# OttoPi08-RPi3AHAT.net
KiCad netlist of a schematic drawn in EAGLE
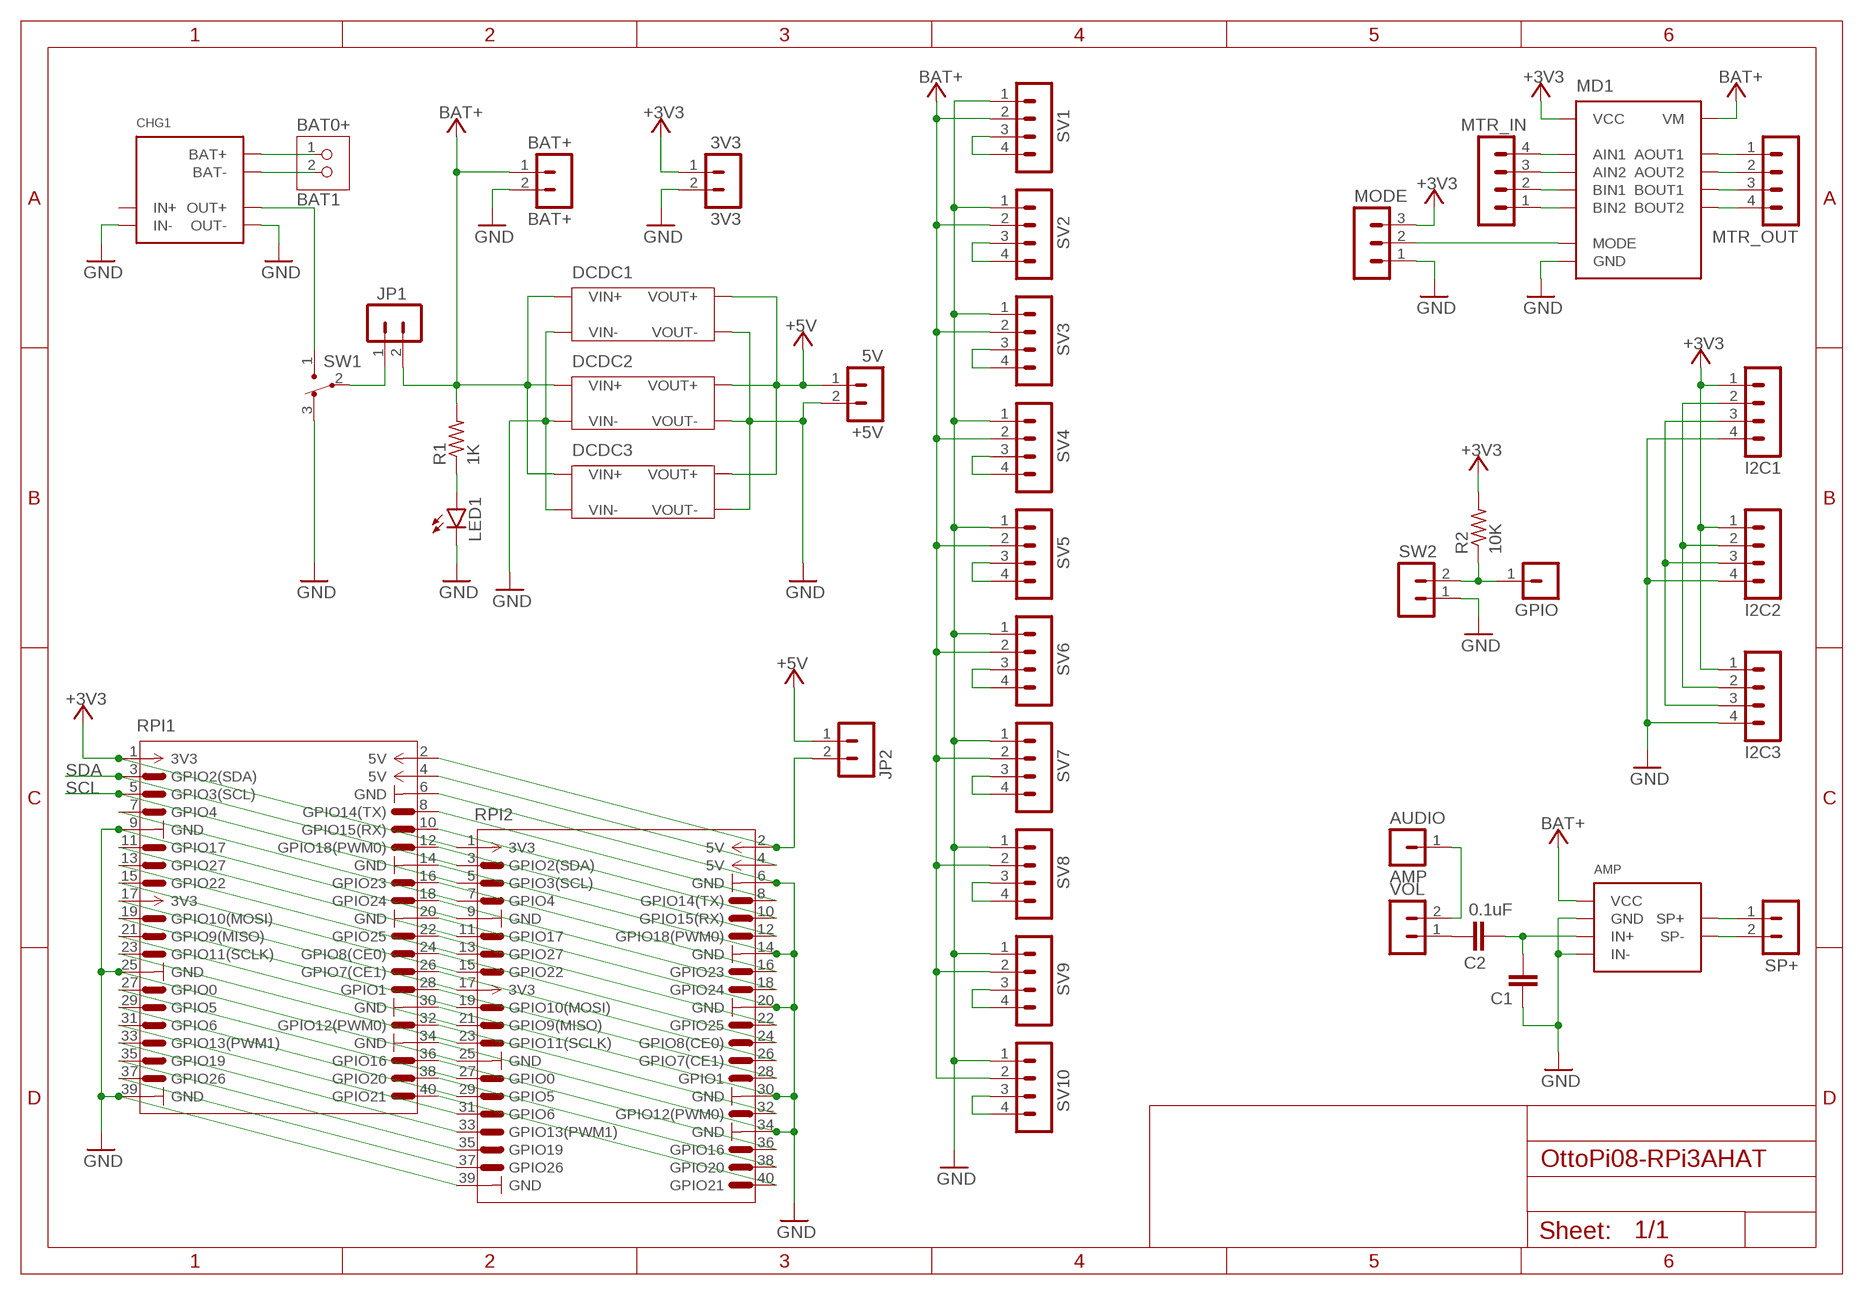
[diagram p0: schematic, sheet 1]

(export (version "E")
  (design (tool "Eeschema 10.0.6"))
  (components
    (comp (ref "+5V")
      (value "5V")
      (footprint "eagle-import:PINHEAD-MA02-1")
      (libsource (lib "eagle-import") (part "PINHEAD-MA02-1"))
    )
    (comp (ref "3V3")
      (value "3V3")
      (footprint "eagle-import:PINHEAD-MA02-1")
      (libsource (lib "eagle-import") (part "PINHEAD-MA02-1"))
    )
    (comp (ref "AMP")
      (value "AMP")
      (footprint "eagle-import:PAM8012MOD-A")
      (libsource (lib "eagle-import") (part "PAM8012MOD"))
    )
    (comp (ref "AUDIO")
      (value "AMP")
      (footprint "eagle-import:PINHEAD-MA01-1")
      (libsource (lib "eagle-import") (part "PINHEAD-MA01-1"))
    )
    (comp (ref "BAT+")
      (value "BAT+")
      (footprint "eagle-import:PINHEAD-MA02-1")
      (libsource (lib "eagle-import") (part "PINHEAD-MA02-1"))
    )
    (comp (ref "BAT0+")
      (value "BAT1")
      (footprint "eagle-import:JST-PH2")
      (libsource (lib "eagle-import") (part "JST-PH2"))
    )
    (comp (ref "C1")
      (value "C-EU025-024X044")
      (footprint "eagle-import:C025-024X044")
      (libsource (lib "eagle-import") (part "C-EU025-024X044"))
    )
    (comp (ref "C2")
      (value "0.1uF")
      (footprint "eagle-import:C025-024X044")
      (libsource (lib "eagle-import") (part "C-EU025-024X044"))
    )
    (comp (ref "CHG1")
      (value "TP4056MOD1")
      (footprint "eagle-import:TP4056MOD1")
      (libsource (lib "eagle-import") (part "TP4056MOD1"))
    )
    (comp (ref "DCDC1")
      (value "DCDC-MT3608-MOD")
      (footprint "eagle-import:DCDC-MT3608-MOD1")
      (libsource (lib "eagle-import") (part "DCDC-MT3608-MOD"))
    )
    (comp (ref "DCDC2")
      (value "DCDC-SX1308-MOD1")
      (footprint "eagle-import:DCDC-SX1308-MOD1")
      (libsource (lib "eagle-import") (part "DCDC-SX1308-MOD1"))
    )
    (comp (ref "DCDC3")
      (value "DCDC-MT3608-MODUSB")
      (footprint "eagle-import:DCDC-MT3608-MOD2-USB")
      (libsource (lib "eagle-import") (part "DCDC-MT3608-MODUSB"))
    )
    (comp (ref "GPIO")
      (value "PINHEAD-MA01-1")
      (footprint "eagle-import:PINHEAD-MA01-1")
      (libsource (lib "eagle-import") (part "PINHEAD-MA01-1"))
    )
    (comp (ref "I2C1")
      (value "PINHEAD-MA04-1")
      (footprint "eagle-import:PINHEAD-MA04-1")
      (libsource (lib "eagle-import") (part "PINHEAD-MA04-1"))
    )
    (comp (ref "I2C2")
      (value "PINHEAD-MA04-1")
      (footprint "eagle-import:PINHEAD-MA04-1")
      (libsource (lib "eagle-import") (part "PINHEAD-MA04-1"))
    )
    (comp (ref "I2C3")
      (value "PINHEAD-MA04-1")
      (footprint "eagle-import:PINHEAD-MA04-1")
      (libsource (lib "eagle-import") (part "PINHEAD-MA04-1"))
    )
    (comp (ref "JP1")
      (value "PINHEAD-MA02-1")
      (footprint "eagle-import:PINHEAD-MA02-1")
      (libsource (lib "eagle-import") (part "PINHEAD-MA02-1"))
    )
    (comp (ref "JP2")
      (value "PINHEAD-MA02-1")
      (footprint "eagle-import:PINHEAD-MA02-1")
      (libsource (lib "eagle-import") (part "PINHEAD-MA02-1"))
    )
    (comp (ref "LED1")
      (value "LED3MM")
      (footprint "eagle-import:LED3MM")
      (libsource (lib "eagle-import") (part "LED3MM"))
    )
    (comp (ref "MD1")
      (value "DRV8835MOD")
      (footprint "eagle-import:DRV8835MOD")
      (libsource (lib "eagle-import") (part "DRV8835MOD"))
    )
    (comp (ref "MODE")
      (value "PINHEAD-MA03-1")
      (footprint "eagle-import:PINHEAD-MA03-1")
      (libsource (lib "eagle-import") (part "PINHEAD-MA03-1"))
    )
    (comp (ref "MTR_IN")
      (value "PINHEAD-MA04-1")
      (footprint "eagle-import:PINHEAD-MA04-1")
      (libsource (lib "eagle-import") (part "PINHEAD-MA04-1"))
    )
    (comp (ref "MTR_OUT")
      (value "PINHEAD-MA04-1")
      (footprint "eagle-import:PINHEAD-MA04-1")
      (libsource (lib "eagle-import") (part "PINHEAD-MA04-1"))
    )
    (comp (ref "R1")
      (value "1K")
      (footprint "eagle-import:0204_7")
      (libsource (lib "eagle-import") (part "R-US_0204/7"))
    )
    (comp (ref "R2")
      (value "10K")
      (footprint "eagle-import:0204_7")
      (libsource (lib "eagle-import") (part "R-US_0204/7"))
    )
    (comp (ref "RPI1")
      (value "RPI-PIN")
      (footprint "eagle-import:RPI-PIN")
      (libsource (lib "eagle-import") (part "RPI-PIN"))
    )
    (comp (ref "RPI2")
      (value "RPI-PIN")
      (footprint "eagle-import:RPI-PIN")
      (libsource (lib "eagle-import") (part "RPI-PIN"))
    )
    (comp (ref "SP+")
      (value "PINHEAD-MA02-1")
      (footprint "eagle-import:PINHEAD-MA02-1")
      (libsource (lib "eagle-import") (part "PINHEAD-MA02-1"))
    )
    (comp (ref "SV1")
      (value "PINHEAD-MA04-1")
      (footprint "eagle-import:PINHEAD-MA04-1")
      (libsource (lib "eagle-import") (part "PINHEAD-MA04-1"))
    )
    (comp (ref "SV2")
      (value "PINHEAD-MA04-1")
      (footprint "eagle-import:PINHEAD-MA04-1")
      (libsource (lib "eagle-import") (part "PINHEAD-MA04-1"))
    )
    (comp (ref "SV3")
      (value "PINHEAD-MA04-1")
      (footprint "eagle-import:PINHEAD-MA04-1")
      (libsource (lib "eagle-import") (part "PINHEAD-MA04-1"))
    )
    (comp (ref "SV4")
      (value "PINHEAD-MA04-1")
      (footprint "eagle-import:PINHEAD-MA04-1")
      (libsource (lib "eagle-import") (part "PINHEAD-MA04-1"))
    )
    (comp (ref "SV5")
      (value "PINHEAD-MA04-1")
      (footprint "eagle-import:PINHEAD-MA04-1")
      (libsource (lib "eagle-import") (part "PINHEAD-MA04-1"))
    )
    (comp (ref "SV6")
      (value "PINHEAD-MA04-1")
      (footprint "eagle-import:PINHEAD-MA04-1")
      (libsource (lib "eagle-import") (part "PINHEAD-MA04-1"))
    )
    (comp (ref "SV7")
      (value "PINHEAD-MA04-1")
      (footprint "eagle-import:PINHEAD-MA04-1")
      (libsource (lib "eagle-import") (part "PINHEAD-MA04-1"))
    )
    (comp (ref "SV8")
      (value "PINHEAD-MA04-1")
      (footprint "eagle-import:PINHEAD-MA04-1")
      (libsource (lib "eagle-import") (part "PINHEAD-MA04-1"))
    )
    (comp (ref "SV9")
      (value "PINHEAD-MA04-1")
      (footprint "eagle-import:PINHEAD-MA04-1")
      (libsource (lib "eagle-import") (part "PINHEAD-MA04-1"))
    )
    (comp (ref "SV10")
      (value "PINHEAD-MA04-1")
      (footprint "eagle-import:PINHEAD-MA04-1")
      (libsource (lib "eagle-import") (part "PINHEAD-MA04-1"))
    )
    (comp (ref "SW1")
      (value "SW3-1")
      (footprint "eagle-import:SW3-1")
      (fields (field (name "MF") "HiLetgo"))
      (libsource (lib "eagle-import") (part "SW3-1"))
    )
    (comp (ref "SW2")
      (value "PINHEAD-MA02-1")
      (footprint "eagle-import:PINHEAD-MA02-1")
      (libsource (lib "eagle-import") (part "PINHEAD-MA02-1"))
    )
    (comp (ref "VOL")
      (value "PINHEAD-MA02-1")
      (footprint "eagle-import:PINHEAD-MA02-1")
      (libsource (lib "eagle-import") (part "PINHEAD-MA02-1"))
    )
  )
  (nets
    (net (code "1") (name "+3V3") (class "Default")
      (node (ref "3V3") (pin "1") (pinfunction "1_1") (pintype "passive"))
      (node (ref "I2C1") (pin "1") (pinfunction "1_1") (pintype "passive"))
      (node (ref "I2C2") (pin "1") (pinfunction "1_1") (pintype "passive"))
      (node (ref "I2C3") (pin "1") (pinfunction "1_1") (pintype "passive"))
      (node (ref "MD1") (pin "VCC") (pinfunction "VCC_VCC") (pintype "input"))
      (node (ref "MODE") (pin "3") (pinfunction "3_3") (pintype "passive"))
      (node (ref "R2") (pin "2") (pinfunction "2_2") (pintype "passive"))
      (node (ref "RPI1") (pin "1") (pinfunction "3V3_1") (pintype "passive"))
      (node (ref "RPI2") (pin "1") (pinfunction "3V3_1") (pintype "passive"))
    )
    (net (code "2") (name "+5V") (class "Default")
      (node (ref "+5V") (pin "1") (pinfunction "1_1") (pintype "passive"))
      (node (ref "DCDC1") (pin "VOUT+") (pinfunction "VOUT+_VOUT+") (pintype "power_in"))
      (node (ref "DCDC2") (pin "VOUT+") (pinfunction "VOUT+_VOUT+") (pintype "power_in"))
      (node (ref "DCDC3") (pin "VOUT+") (pinfunction "VOUT+_VOUT+") (pintype "power_in"))
      (node (ref "JP2") (pin "1") (pinfunction "1_1") (pintype "passive"))
    )
    (net (code "3") (name "/SCL") (class "Default")
      (node (ref "I2C1") (pin "3") (pinfunction "3_3") (pintype "passive"))
      (node (ref "I2C2") (pin "3") (pinfunction "3_3") (pintype "passive"))
      (node (ref "I2C3") (pin "3") (pinfunction "3_3") (pintype "passive"))
      (node (ref "RPI1") (pin "5") (pinfunction "GPIO3(SCL)_5") (pintype "passive"))
      (node (ref "RPI2") (pin "5") (pinfunction "GPIO3(SCL)_5") (pintype "passive"))
    )
    (net (code "4") (name "/SDA") (class "Default")
      (node (ref "I2C1") (pin "2") (pinfunction "2_2") (pintype "passive"))
      (node (ref "I2C2") (pin "2") (pinfunction "2_2") (pintype "passive"))
      (node (ref "I2C3") (pin "2") (pinfunction "2_2") (pintype "passive"))
      (node (ref "RPI1") (pin "3") (pinfunction "GPIO2(SDA)_3") (pintype "passive"))
      (node (ref "RPI2") (pin "3") (pinfunction "GPIO2(SDA)_3") (pintype "passive"))
    )
    (net (code "5") (name "BAT+") (class "Default")
      (node (ref "AMP") (pin "V+") (pinfunction "VCC_V+") (pintype "passive"))
      (node (ref "BAT+") (pin "1") (pinfunction "1_1") (pintype "passive"))
      (node (ref "DCDC1") (pin "VIN+") (pinfunction "VIN+_VIN+") (pintype "power_in"))
      (node (ref "DCDC2") (pin "VIN+") (pinfunction "VIN+_VIN+") (pintype "power_in"))
      (node (ref "DCDC3") (pin "VIN+") (pinfunction "VIN+_VIN+") (pintype "power_in"))
      (node (ref "JP1") (pin "2") (pinfunction "2_2") (pintype "passive"))
      (node (ref "MD1") (pin "VM") (pinfunction "VM_VM") (pintype "input"))
      (node (ref "R1") (pin "2") (pinfunction "2_2") (pintype "passive"))
      (node (ref "SV1") (pin "2") (pinfunction "2_2") (pintype "passive"))
      (node (ref "SV10") (pin "2") (pinfunction "2_2") (pintype "passive"))
      (node (ref "SV2") (pin "2") (pinfunction "2_2") (pintype "passive"))
      (node (ref "SV3") (pin "2") (pinfunction "2_2") (pintype "passive"))
      (node (ref "SV4") (pin "2") (pinfunction "2_2") (pintype "passive"))
      (node (ref "SV5") (pin "2") (pinfunction "2_2") (pintype "passive"))
      (node (ref "SV6") (pin "2") (pinfunction "2_2") (pintype "passive"))
      (node (ref "SV7") (pin "2") (pinfunction "2_2") (pintype "passive"))
      (node (ref "SV8") (pin "2") (pinfunction "2_2") (pintype "passive"))
      (node (ref "SV9") (pin "2") (pinfunction "2_2") (pintype "passive"))
    )
    (net (code "6") (name "GND") (class "Default")
      (node (ref "+5V") (pin "2") (pinfunction "2_2") (pintype "passive"))
      (node (ref "3V3") (pin "2") (pinfunction "2_2") (pintype "passive"))
      (node (ref "AMP") (pin "GND") (pinfunction "GND_GND") (pintype "passive"))
      (node (ref "AMP") (pin "IN-") (pinfunction "IN-_IN-") (pintype "input"))
      (node (ref "BAT+") (pin "2") (pinfunction "2_2") (pintype "passive"))
      (node (ref "C1") (pin "1") (pinfunction "1_1") (pintype "passive"))
      (node (ref "CHG1") (pin "IN-") (pinfunction "IN-_IN-") (pintype "passive"))
      (node (ref "CHG1") (pin "OUT-") (pinfunction "OUT-_OUT-") (pintype "passive"))
      (node (ref "DCDC1") (pin "VIN-") (pinfunction "VIN-_VIN-") (pintype "power_in"))
      (node (ref "DCDC1") (pin "VOUT-") (pinfunction "VOUT-_VOUT-") (pintype "power_in"))
      (node (ref "DCDC2") (pin "VIN-") (pinfunction "VIN-_VIN-") (pintype "power_in"))
      (node (ref "DCDC2") (pin "VOUT-") (pinfunction "VOUT-_VOUT-") (pintype "power_in"))
      (node (ref "DCDC3") (pin "VIN-") (pinfunction "VIN-_VIN-") (pintype "power_in"))
      (node (ref "DCDC3") (pin "VOUT-") (pinfunction "VOUT-_VOUT-") (pintype "power_in"))
      (node (ref "I2C1") (pin "4") (pinfunction "4_4") (pintype "passive"))
      (node (ref "I2C2") (pin "4") (pinfunction "4_4") (pintype "passive"))
      (node (ref "I2C3") (pin "4") (pinfunction "4_4") (pintype "passive"))
      (node (ref "LED1") (pin "K") (pinfunction "C_K") (pintype "passive"))
      (node (ref "MD1") (pin "GND") (pinfunction "GND_GND") (pintype "power_in"))
      (node (ref "MODE") (pin "1") (pinfunction "1_1") (pintype "passive"))
      (node (ref "RPI1") (pin "14") (pinfunction "GND_14") (pintype "passive"))
      (node (ref "RPI1") (pin "20") (pinfunction "GND_20") (pintype "passive"))
      (node (ref "RPI1") (pin "25") (pinfunction "GND_25") (pintype "passive"))
      (node (ref "RPI1") (pin "30") (pinfunction "GND_30") (pintype "passive"))
      (node (ref "RPI1") (pin "34") (pinfunction "GND_34") (pintype "passive"))
      (node (ref "RPI1") (pin "39") (pinfunction "GND_39") (pintype "passive"))
      (node (ref "RPI1") (pin "6") (pinfunction "GND_6") (pintype "passive"))
      (node (ref "RPI1") (pin "9") (pinfunction "GND_9") (pintype "passive"))
      (node (ref "RPI2") (pin "14") (pinfunction "GND_14") (pintype "passive"))
      (node (ref "RPI2") (pin "20") (pinfunction "GND_20") (pintype "passive"))
      (node (ref "RPI2") (pin "25") (pinfunction "GND_25") (pintype "passive"))
      (node (ref "RPI2") (pin "30") (pinfunction "GND_30") (pintype "passive"))
      (node (ref "RPI2") (pin "34") (pinfunction "GND_34") (pintype "passive"))
      (node (ref "RPI2") (pin "39") (pinfunction "GND_39") (pintype "passive"))
      (node (ref "RPI2") (pin "6") (pinfunction "GND_6") (pintype "passive"))
      (node (ref "RPI2") (pin "9") (pinfunction "GND_9") (pintype "passive"))
      (node (ref "SV1") (pin "1") (pinfunction "1_1") (pintype "passive"))
      (node (ref "SV10") (pin "1") (pinfunction "1_1") (pintype "passive"))
      (node (ref "SV2") (pin "1") (pinfunction "1_1") (pintype "passive"))
      (node (ref "SV3") (pin "1") (pinfunction "1_1") (pintype "passive"))
      (node (ref "SV4") (pin "1") (pinfunction "1_1") (pintype "passive"))
      (node (ref "SV5") (pin "1") (pinfunction "1_1") (pintype "passive"))
      (node (ref "SV6") (pin "1") (pinfunction "1_1") (pintype "passive"))
      (node (ref "SV7") (pin "1") (pinfunction "1_1") (pintype "passive"))
      (node (ref "SV8") (pin "1") (pinfunction "1_1") (pintype "passive"))
      (node (ref "SV9") (pin "1") (pinfunction "1_1") (pintype "passive"))
      (node (ref "SW1") (pin "3") (pinfunction "3_3") (pintype "passive"))
      (node (ref "SW2") (pin "1") (pinfunction "1_1") (pintype "passive"))
    )
    (net (code "7") (name "Net-(AMP-PadIN+)") (class "Default")
      (node (ref "AMP") (pin "IN+") (pinfunction "IN+_IN+") (pintype "input"))
      (node (ref "C1") (pin "2") (pinfunction "2_2") (pintype "passive"))
      (node (ref "C2") (pin "1") (pinfunction "1_1") (pintype "passive"))
    )
    (net (code "8") (name "Net-(AMP-SP+)") (class "Default")
      (node (ref "AMP") (pin "SP+@1") (pinfunction "SP+_SP+@1") (pintype "output"))
      (node (ref "SP+") (pin "1") (pinfunction "1_1") (pintype "passive"))
    )
    (net (code "9") (name "Net-(AMP-SP-)") (class "Default")
      (node (ref "AMP") (pin "SP-@1") (pinfunction "SP-_SP-@1") (pintype "output"))
      (node (ref "SP+") (pin "2") (pinfunction "2_2") (pintype "passive"))
    )
    (net (code "10") (name "Net-(AUDIO-Pad1)") (class "Default")
      (node (ref "AUDIO") (pin "1") (pinfunction "1_1") (pintype "passive"))
      (node (ref "VOL") (pin "2") (pinfunction "2_2") (pintype "passive"))
    )
    (net (code "11") (name "Net-(BAT0+-Pad1)") (class "Default")
      (node (ref "BAT0+") (pin "1") (pinfunction "1_1") (pintype "passive"))
      (node (ref "CHG1") (pin "BAT+") (pinfunction "BAT+_BAT+") (pintype "passive"))
    )
    (net (code "12") (name "Net-(BAT0+-Pad2)") (class "Default")
      (node (ref "BAT0+") (pin "2") (pinfunction "2_2") (pintype "passive"))
      (node (ref "CHG1") (pin "BAT-") (pinfunction "BAT-_BAT-") (pintype "passive"))
    )
    (net (code "13") (name "Net-(C2-Pad2)") (class "Default")
      (node (ref "C2") (pin "2") (pinfunction "2_2") (pintype "passive"))
      (node (ref "VOL") (pin "1") (pinfunction "1_1") (pintype "passive"))
    )
    (net (code "14") (name "Net-(CHG1-PadOUT+)") (class "Default")
      (node (ref "CHG1") (pin "OUT+") (pinfunction "OUT+_OUT+") (pintype "passive"))
      (node (ref "SW1") (pin "1") (pinfunction "1_1") (pintype "passive"))
    )
    (net (code "15") (name "Net-(GPIO-Pad1)") (class "Default")
      (node (ref "GPIO") (pin "1") (pinfunction "1_1") (pintype "passive"))
      (node (ref "R2") (pin "1") (pinfunction "1_1") (pintype "passive"))
      (node (ref "SW2") (pin "2") (pinfunction "2_2") (pintype "passive"))
    )
    (net (code "16") (name "Net-(JP1-Pad1)") (class "Default")
      (node (ref "JP1") (pin "1") (pinfunction "1_1") (pintype "passive"))
      (node (ref "SW1") (pin "2") (pinfunction "2_2") (pintype "passive"))
    )
    (net (code "17") (name "Net-(JP2-Pad2)") (class "Default")
      (node (ref "JP2") (pin "2") (pinfunction "2_2") (pintype "passive"))
      (node (ref "RPI1") (pin "2") (pinfunction "5V_2") (pintype "passive"))
      (node (ref "RPI2") (pin "2") (pinfunction "5V_2") (pintype "passive"))
    )
    (net (code "18") (name "Net-(LED1-PadA)") (class "Default")
      (node (ref "LED1") (pin "A") (pinfunction "A_A") (pintype "passive"))
      (node (ref "R1") (pin "1") (pinfunction "1_1") (pintype "passive"))
    )
    (net (code "19") (name "Net-(MD1-PadAIN1)") (class "Default")
      (node (ref "MD1") (pin "AIN1") (pinfunction "AIN1_AIN1") (pintype "input"))
      (node (ref "MTR_IN") (pin "4") (pinfunction "4_4") (pintype "passive"))
    )
    (net (code "20") (name "Net-(MD1-PadAIN2)") (class "Default")
      (node (ref "MD1") (pin "AIN2") (pinfunction "AIN2_AIN2") (pintype "input"))
      (node (ref "MTR_IN") (pin "3") (pinfunction "3_3") (pintype "passive"))
    )
    (net (code "21") (name "Net-(MD1-PadAOUT1)") (class "Default")
      (node (ref "MD1") (pin "AOUT1") (pinfunction "AOUT1_AOUT1") (pintype "output"))
      (node (ref "MTR_OUT") (pin "1") (pinfunction "1_1") (pintype "passive"))
    )
    (net (code "22") (name "Net-(MD1-PadAOUT2)") (class "Default")
      (node (ref "MD1") (pin "AOUT2") (pinfunction "AOUT2_AOUT2") (pintype "output"))
      (node (ref "MTR_OUT") (pin "2") (pinfunction "2_2") (pintype "passive"))
    )
    (net (code "23") (name "Net-(MD1-PadBIN1)") (class "Default")
      (node (ref "MD1") (pin "BIN1") (pinfunction "BIN1_BIN1") (pintype "input"))
      (node (ref "MTR_IN") (pin "2") (pinfunction "2_2") (pintype "passive"))
    )
    (net (code "24") (name "Net-(MD1-PadBIN2)") (class "Default")
      (node (ref "MD1") (pin "BIN2") (pinfunction "BIN2_BIN2") (pintype "input"))
      (node (ref "MTR_IN") (pin "1") (pinfunction "1_1") (pintype "passive"))
    )
    (net (code "25") (name "Net-(MD1-PadBOUT1)") (class "Default")
      (node (ref "MD1") (pin "BOUT1") (pinfunction "BOUT1_BOUT1") (pintype "output"))
      (node (ref "MTR_OUT") (pin "3") (pinfunction "3_3") (pintype "passive"))
    )
    (net (code "26") (name "Net-(MD1-PadBOUT2)") (class "Default")
      (node (ref "MD1") (pin "BOUT2") (pinfunction "BOUT2_BOUT2") (pintype "output"))
      (node (ref "MTR_OUT") (pin "4") (pinfunction "4_4") (pintype "passive"))
    )
    (net (code "27") (name "Net-(MD1-PadMODE)") (class "Default")
      (node (ref "MD1") (pin "MODE") (pinfunction "MODE_MODE") (pintype "input"))
      (node (ref "MODE") (pin "2") (pinfunction "2_2") (pintype "passive"))
    )
    (net (code "28") (name "Net-(RPI1-3V3-Pad17)") (class "Default")
      (node (ref "RPI1") (pin "17") (pinfunction "3V3_17") (pintype "passive"))
      (node (ref "RPI2") (pin "17") (pinfunction "3V3_17") (pintype "passive"))
    )
    (net (code "29") (name "Net-(RPI1-5V-Pad4)") (class "Default")
      (node (ref "RPI1") (pin "4") (pinfunction "5V_4") (pintype "passive"))
      (node (ref "RPI2") (pin "4") (pinfunction "5V_4") (pintype "passive"))
    )
    (net (code "30") (name "Net-(RPI1-GPIO0)") (class "Default")
      (node (ref "RPI1") (pin "27") (pinfunction "GPIO0_27") (pintype "passive"))
      (node (ref "RPI2") (pin "27") (pinfunction "GPIO0_27") (pintype "passive"))
    )
    (net (code "31") (name "Net-(RPI1-GPIO1)") (class "Default")
      (node (ref "RPI1") (pin "28") (pinfunction "GPIO1_28") (pintype "passive"))
      (node (ref "RPI2") (pin "28") (pinfunction "GPIO1_28") (pintype "passive"))
    )
    (net (code "32") (name "Net-(RPI1-GPIO4)") (class "Default")
      (node (ref "RPI1") (pin "7") (pinfunction "GPIO4_7") (pintype "passive"))
      (node (ref "RPI2") (pin "7") (pinfunction "GPIO4_7") (pintype "passive"))
    )
    (net (code "33") (name "Net-(RPI1-GPIO5)") (class "Default")
      (node (ref "RPI1") (pin "29") (pinfunction "GPIO5_29") (pintype "passive"))
      (node (ref "RPI2") (pin "29") (pinfunction "GPIO5_29") (pintype "passive"))
    )
    (net (code "34") (name "Net-(RPI1-GPIO6)") (class "Default")
      (node (ref "RPI1") (pin "31") (pinfunction "GPIO6_31") (pintype "passive"))
      (node (ref "RPI2") (pin "31") (pinfunction "GPIO6_31") (pintype "passive"))
    )
    (net (code "35") (name "Net-(RPI1-GPIO7(CE1))") (class "Default")
      (node (ref "RPI1") (pin "26") (pinfunction "GPIO7(CE1)_26") (pintype "passive"))
      (node (ref "RPI2") (pin "26") (pinfunction "GPIO7(CE1)_26") (pintype "passive"))
    )
    (net (code "36") (name "Net-(RPI1-GPIO8(CE0))") (class "Default")
      (node (ref "RPI1") (pin "24") (pinfunction "GPIO8(CE0)_24") (pintype "passive"))
      (node (ref "RPI2") (pin "24") (pinfunction "GPIO8(CE0)_24") (pintype "passive"))
    )
    (net (code "37") (name "Net-(RPI1-GPIO9(MISO))") (class "Default")
      (node (ref "RPI1") (pin "21") (pinfunction "GPIO9(MISO)_21") (pintype "passive"))
      (node (ref "RPI2") (pin "21") (pinfunction "GPIO9(MISO)_21") (pintype "passive"))
    )
    (net (code "38") (name "Net-(RPI1-GPIO10(MOSI))") (class "Default")
      (node (ref "RPI1") (pin "19") (pinfunction "GPIO10(MOSI)_19") (pintype "passive"))
      (node (ref "RPI2") (pin "19") (pinfunction "GPIO10(MOSI)_19") (pintype "passive"))
    )
    (net (code "39") (name "Net-(RPI1-GPIO11(SCLK))") (class "Default")
      (node (ref "RPI1") (pin "23") (pinfunction "GPIO11(SCLK)_23") (pintype "passive"))
      (node (ref "RPI2") (pin "23") (pinfunction "GPIO11(SCLK)_23") (pintype "passive"))
    )
    (net (code "40") (name "Net-(RPI1-GPIO12(PWM0))") (class "Default")
      (node (ref "RPI1") (pin "32") (pinfunction "GPIO12(PWM0)_32") (pintype "passive"))
      (node (ref "RPI2") (pin "32") (pinfunction "GPIO12(PWM0)_32") (pintype "passive"))
    )
    (net (code "41") (name "Net-(RPI1-GPIO13(PWM1))") (class "Default")
      (node (ref "RPI1") (pin "33") (pinfunction "GPIO13(PWM1)_33") (pintype "passive"))
      (node (ref "RPI2") (pin "33") (pinfunction "GPIO13(PWM1)_33") (pintype "passive"))
    )
    (net (code "42") (name "Net-(RPI1-GPIO14(TX))") (class "Default")
      (node (ref "RPI1") (pin "8") (pinfunction "GPIO14(TX)_8") (pintype "passive"))
      (node (ref "RPI2") (pin "8") (pinfunction "GPIO14(TX)_8") (pintype "passive"))
    )
    (net (code "43") (name "Net-(RPI1-GPIO15(RX))") (class "Default")
      (node (ref "RPI1") (pin "10") (pinfunction "GPIO15(RX)_10") (pintype "passive"))
      (node (ref "RPI2") (pin "10") (pinfunction "GPIO15(RX)_10") (pintype "passive"))
    )
    (net (code "44") (name "Net-(RPI1-GPIO16)") (class "Default")
      (node (ref "RPI1") (pin "36") (pinfunction "GPIO16_36") (pintype "passive"))
      (node (ref "RPI2") (pin "36") (pinfunction "GPIO16_36") (pintype "passive"))
    )
    (net (code "45") (name "Net-(RPI1-GPIO17)") (class "Default")
      (node (ref "RPI1") (pin "11") (pinfunction "GPIO17_11") (pintype "passive"))
      (node (ref "RPI2") (pin "11") (pinfunction "GPIO17_11") (pintype "passive"))
    )
    (net (code "46") (name "Net-(RPI1-GPIO18(PWM0))") (class "Default")
      (node (ref "RPI1") (pin "12") (pinfunction "GPIO18(PWM0)_12") (pintype "passive"))
      (node (ref "RPI2") (pin "12") (pinfunction "GPIO18(PWM0)_12") (pintype "passive"))
    )
    (net (code "47") (name "Net-(RPI1-GPIO19)") (class "Default")
      (node (ref "RPI1") (pin "35") (pinfunction "GPIO19_35") (pintype "passive"))
      (node (ref "RPI2") (pin "35") (pinfunction "GPIO19_35") (pintype "passive"))
    )
    (net (code "48") (name "Net-(RPI1-GPIO20)") (class "Default")
      (node (ref "RPI1") (pin "38") (pinfunction "GPIO20_38") (pintype "passive"))
      (node (ref "RPI2") (pin "38") (pinfunction "GPIO20_38") (pintype "passive"))
    )
    (net (code "49") (name "Net-(RPI1-GPIO21)") (class "Default")
      (node (ref "RPI1") (pin "40") (pinfunction "GPIO21_40") (pintype "passive"))
      (node (ref "RPI2") (pin "40") (pinfunction "GPIO21_40") (pintype "passive"))
    )
    (net (code "50") (name "Net-(RPI1-GPIO22)") (class "Default")
      (node (ref "RPI1") (pin "15") (pinfunction "GPIO22_15") (pintype "passive"))
      (node (ref "RPI2") (pin "15") (pinfunction "GPIO22_15") (pintype "passive"))
    )
    (net (code "51") (name "Net-(RPI1-GPIO23)") (class "Default")
      (node (ref "RPI1") (pin "16") (pinfunction "GPIO23_16") (pintype "passive"))
      (node (ref "RPI2") (pin "16") (pinfunction "GPIO23_16") (pintype "passive"))
    )
    (net (code "52") (name "Net-(RPI1-GPIO24)") (class "Default")
      (node (ref "RPI1") (pin "18") (pinfunction "GPIO24_18") (pintype "passive"))
      (node (ref "RPI2") (pin "18") (pinfunction "GPIO24_18") (pintype "passive"))
    )
    (net (code "53") (name "Net-(RPI1-GPIO25)") (class "Default")
      (node (ref "RPI1") (pin "22") (pinfunction "GPIO25_22") (pintype "passive"))
      (node (ref "RPI2") (pin "22") (pinfunction "GPIO25_22") (pintype "passive"))
    )
    (net (code "54") (name "Net-(RPI1-GPIO26)") (class "Default")
      (node (ref "RPI1") (pin "37") (pinfunction "GPIO26_37") (pintype "passive"))
      (node (ref "RPI2") (pin "37") (pinfunction "GPIO26_37") (pintype "passive"))
    )
    (net (code "55") (name "Net-(RPI1-GPIO27)") (class "Default")
      (node (ref "RPI1") (pin "13") (pinfunction "GPIO27_13") (pintype "passive"))
      (node (ref "RPI2") (pin "13") (pinfunction "GPIO27_13") (pintype "passive"))
    )
    (net (code "56") (name "Net-(SV1-Pad3)") (class "Default")
      (node (ref "SV1") (pin "3") (pinfunction "3_3") (pintype "passive"))
      (node (ref "SV1") (pin "4") (pinfunction "4_4") (pintype "passive"))
    )
    (net (code "57") (name "Net-(SV2-Pad3)") (class "Default")
      (node (ref "SV2") (pin "3") (pinfunction "3_3") (pintype "passive"))
      (node (ref "SV2") (pin "4") (pinfunction "4_4") (pintype "passive"))
    )
    (net (code "58") (name "Net-(SV3-Pad3)") (class "Default")
      (node (ref "SV3") (pin "3") (pinfunction "3_3") (pintype "passive"))
      (node (ref "SV3") (pin "4") (pinfunction "4_4") (pintype "passive"))
    )
    (net (code "59") (name "Net-(SV4-Pad3)") (class "Default")
      (node (ref "SV4") (pin "3") (pinfunction "3_3") (pintype "passive"))
      (node (ref "SV4") (pin "4") (pinfunction "4_4") (pintype "passive"))
    )
    (net (code "60") (name "Net-(SV5-Pad3)") (class "Default")
      (node (ref "SV5") (pin "3") (pinfunction "3_3") (pintype "passive"))
      (node (ref "SV5") (pin "4") (pinfunction "4_4") (pintype "passive"))
    )
    (net (code "61") (name "Net-(SV6-Pad3)") (class "Default")
      (node (ref "SV6") (pin "3") (pinfunction "3_3") (pintype "passive"))
      (node (ref "SV6") (pin "4") (pinfunction "4_4") (pintype "passive"))
    )
    (net (code "62") (name "Net-(SV7-Pad3)") (class "Default")
      (node (ref "SV7") (pin "3") (pinfunction "3_3") (pintype "passive"))
      (node (ref "SV7") (pin "4") (pinfunction "4_4") (pintype "passive"))
    )
    (net (code "63") (name "Net-(SV8-Pad3)") (class "Default")
      (node (ref "SV8") (pin "3") (pinfunction "3_3") (pintype "passive"))
      (node (ref "SV8") (pin "4") (pinfunction "4_4") (pintype "passive"))
    )
    (net (code "64") (name "Net-(SV9-Pad3)") (class "Default")
      (node (ref "SV9") (pin "3") (pinfunction "3_3") (pintype "passive"))
      (node (ref "SV9") (pin "4") (pinfunction "4_4") (pintype "passive"))
    )
    (net (code "65") (name "Net-(SV10-Pad3)") (class "Default")
      (node (ref "SV10") (pin "3") (pinfunction "3_3") (pintype "passive"))
      (node (ref "SV10") (pin "4") (pinfunction "4_4") (pintype "passive"))
    )
    (net (code "66") (name "unconnected-(CHG1-PadIN+)") (class "Default")
      (node (ref "CHG1") (pin "IN+") (pinfunction "IN+_IN+") (pintype "passive"))
    )
  )
)
